# PLMGTBanks.net
KiCad netlist of a schematic drawn in Altium Designer
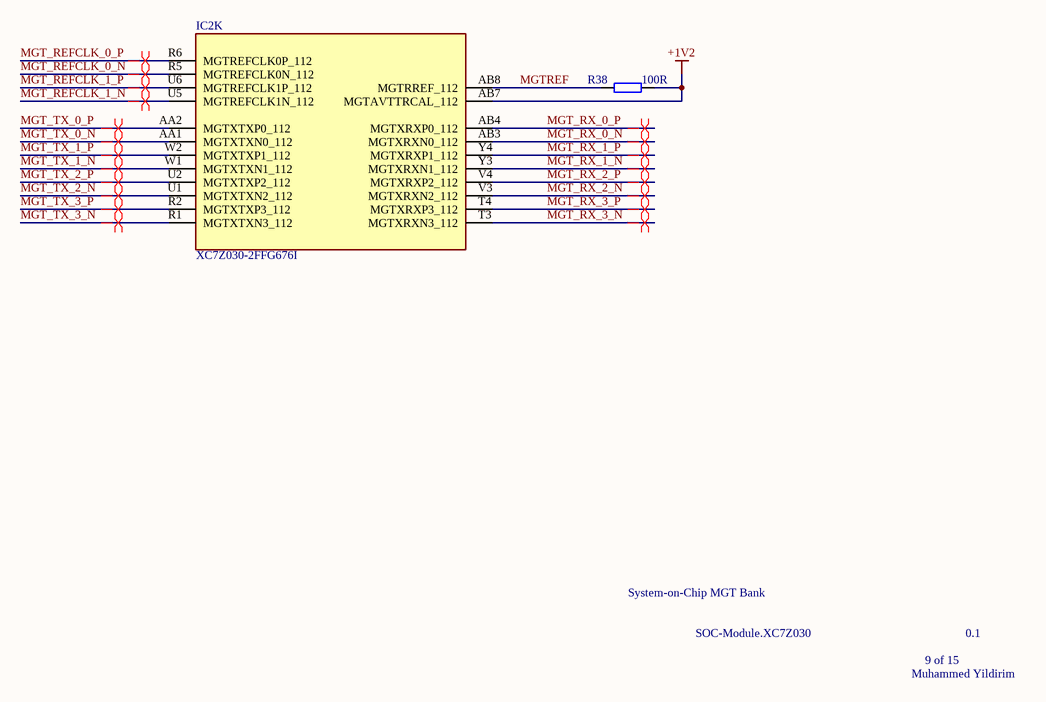
[diagram p0: PLMGTBanks.SchDoc]

(export (version "E")
  (design (tool "Eeschema 10.0.6"))
  (components
    (comp (ref "IC2")
      (value "XC7Z030-2FFG676I")
      (footprint "XC7Z030PCBLib:BGA676C100P26X26_2700X2700X324")
      (description "Integrated Circuit")
      (fields (field (name "MOUSER PART NUMBER") "217-XC7Z030-2FFG676I"))
      (libsource (lib "XC7Z030SCHLib") (part "XC7Z030-2FFG676I"))
    )
    (comp (ref "R38")
      (value "100R")
      (footprint "RES_0201")
      (description "Resistor SMD 0201")
      (libsource (lib "Schematic-Lib-PhilsLab") (part "RES_0201"))
    )
  )
  (nets
    (net (code "1") (name "+1V2") (class "Default")
      (node (ref "IC2") (pin "AB7") (pinfunction "MGTAVTTRCAL_112_AB7") (pintype "passive"))
      (node (ref "R38") (pin "2") (pinfunction "2_2") (pintype "passive"))
    )
    (net (code "2") (name "/MGTREF") (class "Default")
      (node (ref "IC2") (pin "AB8") (pinfunction "MGTRREF_112_AB8") (pintype "passive"))
      (node (ref "R38") (pin "1") (pinfunction "1_1") (pintype "passive"))
    )
    (net (code "3") (name "/MGT_REFCLK_0_N") (class "Default")
      (node (ref "IC2") (pin "R5") (pinfunction "MGTREFCLK0N_112_R5") (pintype "passive"))
    )
    (net (code "4") (name "/MGT_REFCLK_0_P") (class "Default")
      (node (ref "IC2") (pin "R6") (pinfunction "MGTREFCLK0P_112_R6") (pintype "passive"))
    )
    (net (code "5") (name "/MGT_REFCLK_1_N") (class "Default")
      (node (ref "IC2") (pin "U5") (pinfunction "MGTREFCLK1N_112_U5") (pintype "passive"))
    )
    (net (code "6") (name "/MGT_REFCLK_1_P") (class "Default")
      (node (ref "IC2") (pin "U6") (pinfunction "MGTREFCLK1P_112_U6") (pintype "passive"))
    )
    (net (code "7") (name "/MGT_RX_0_N") (class "Default")
      (node (ref "IC2") (pin "AB3") (pinfunction "MGTXRXN0_112_AB3") (pintype "passive"))
    )
    (net (code "8") (name "/MGT_RX_0_P") (class "Default")
      (node (ref "IC2") (pin "AB4") (pinfunction "MGTXRXP0_112_AB4") (pintype "passive"))
    )
    (net (code "9") (name "/MGT_RX_1_N") (class "Default")
      (node (ref "IC2") (pin "Y3") (pinfunction "MGTXRXN1_112_Y3") (pintype "passive"))
    )
    (net (code "10") (name "/MGT_RX_1_P") (class "Default")
      (node (ref "IC2") (pin "Y4") (pinfunction "MGTXRXP1_112_Y4") (pintype "passive"))
    )
    (net (code "11") (name "/MGT_RX_2_N") (class "Default")
      (node (ref "IC2") (pin "V3") (pinfunction "MGTXRXN2_112_V3") (pintype "passive"))
    )
    (net (code "12") (name "/MGT_RX_2_P") (class "Default")
      (node (ref "IC2") (pin "V4") (pinfunction "MGTXRXP2_112_V4") (pintype "passive"))
    )
    (net (code "13") (name "/MGT_RX_3_N") (class "Default")
      (node (ref "IC2") (pin "T3") (pinfunction "MGTXRXN3_112_T3") (pintype "passive"))
    )
    (net (code "14") (name "/MGT_RX_3_P") (class "Default")
      (node (ref "IC2") (pin "T4") (pinfunction "MGTXRXP3_112_T4") (pintype "passive"))
    )
    (net (code "15") (name "/MGT_TX_0_N") (class "Default")
      (node (ref "IC2") (pin "AA1") (pinfunction "MGTXTXN0_112_AA1") (pintype "passive"))
    )
    (net (code "16") (name "/MGT_TX_0_P") (class "Default")
      (node (ref "IC2") (pin "AA2") (pinfunction "MGTXTXP0_112_AA2") (pintype "passive"))
    )
    (net (code "17") (name "/MGT_TX_1_N") (class "Default")
      (node (ref "IC2") (pin "W1") (pinfunction "MGTXTXN1_112_W1") (pintype "passive"))
    )
    (net (code "18") (name "/MGT_TX_1_P") (class "Default")
      (node (ref "IC2") (pin "W2") (pinfunction "MGTXTXP1_112_W2") (pintype "passive"))
    )
    (net (code "19") (name "/MGT_TX_2_N") (class "Default")
      (node (ref "IC2") (pin "U1") (pinfunction "MGTXTXN2_112_U1") (pintype "passive"))
    )
    (net (code "20") (name "/MGT_TX_2_P") (class "Default")
      (node (ref "IC2") (pin "U2") (pinfunction "MGTXTXP2_112_U2") (pintype "passive"))
    )
    (net (code "21") (name "/MGT_TX_3_N") (class "Default")
      (node (ref "IC2") (pin "R1") (pinfunction "MGTXTXN3_112_R1") (pintype "passive"))
    )
    (net (code "22") (name "/MGT_TX_3_P") (class "Default")
      (node (ref "IC2") (pin "R2") (pinfunction "MGTXTXP3_112_R2") (pintype "passive"))
    )
  )
)
